# ntp-strat2.net
KiCad netlist of a schematic drawn in EAGLE
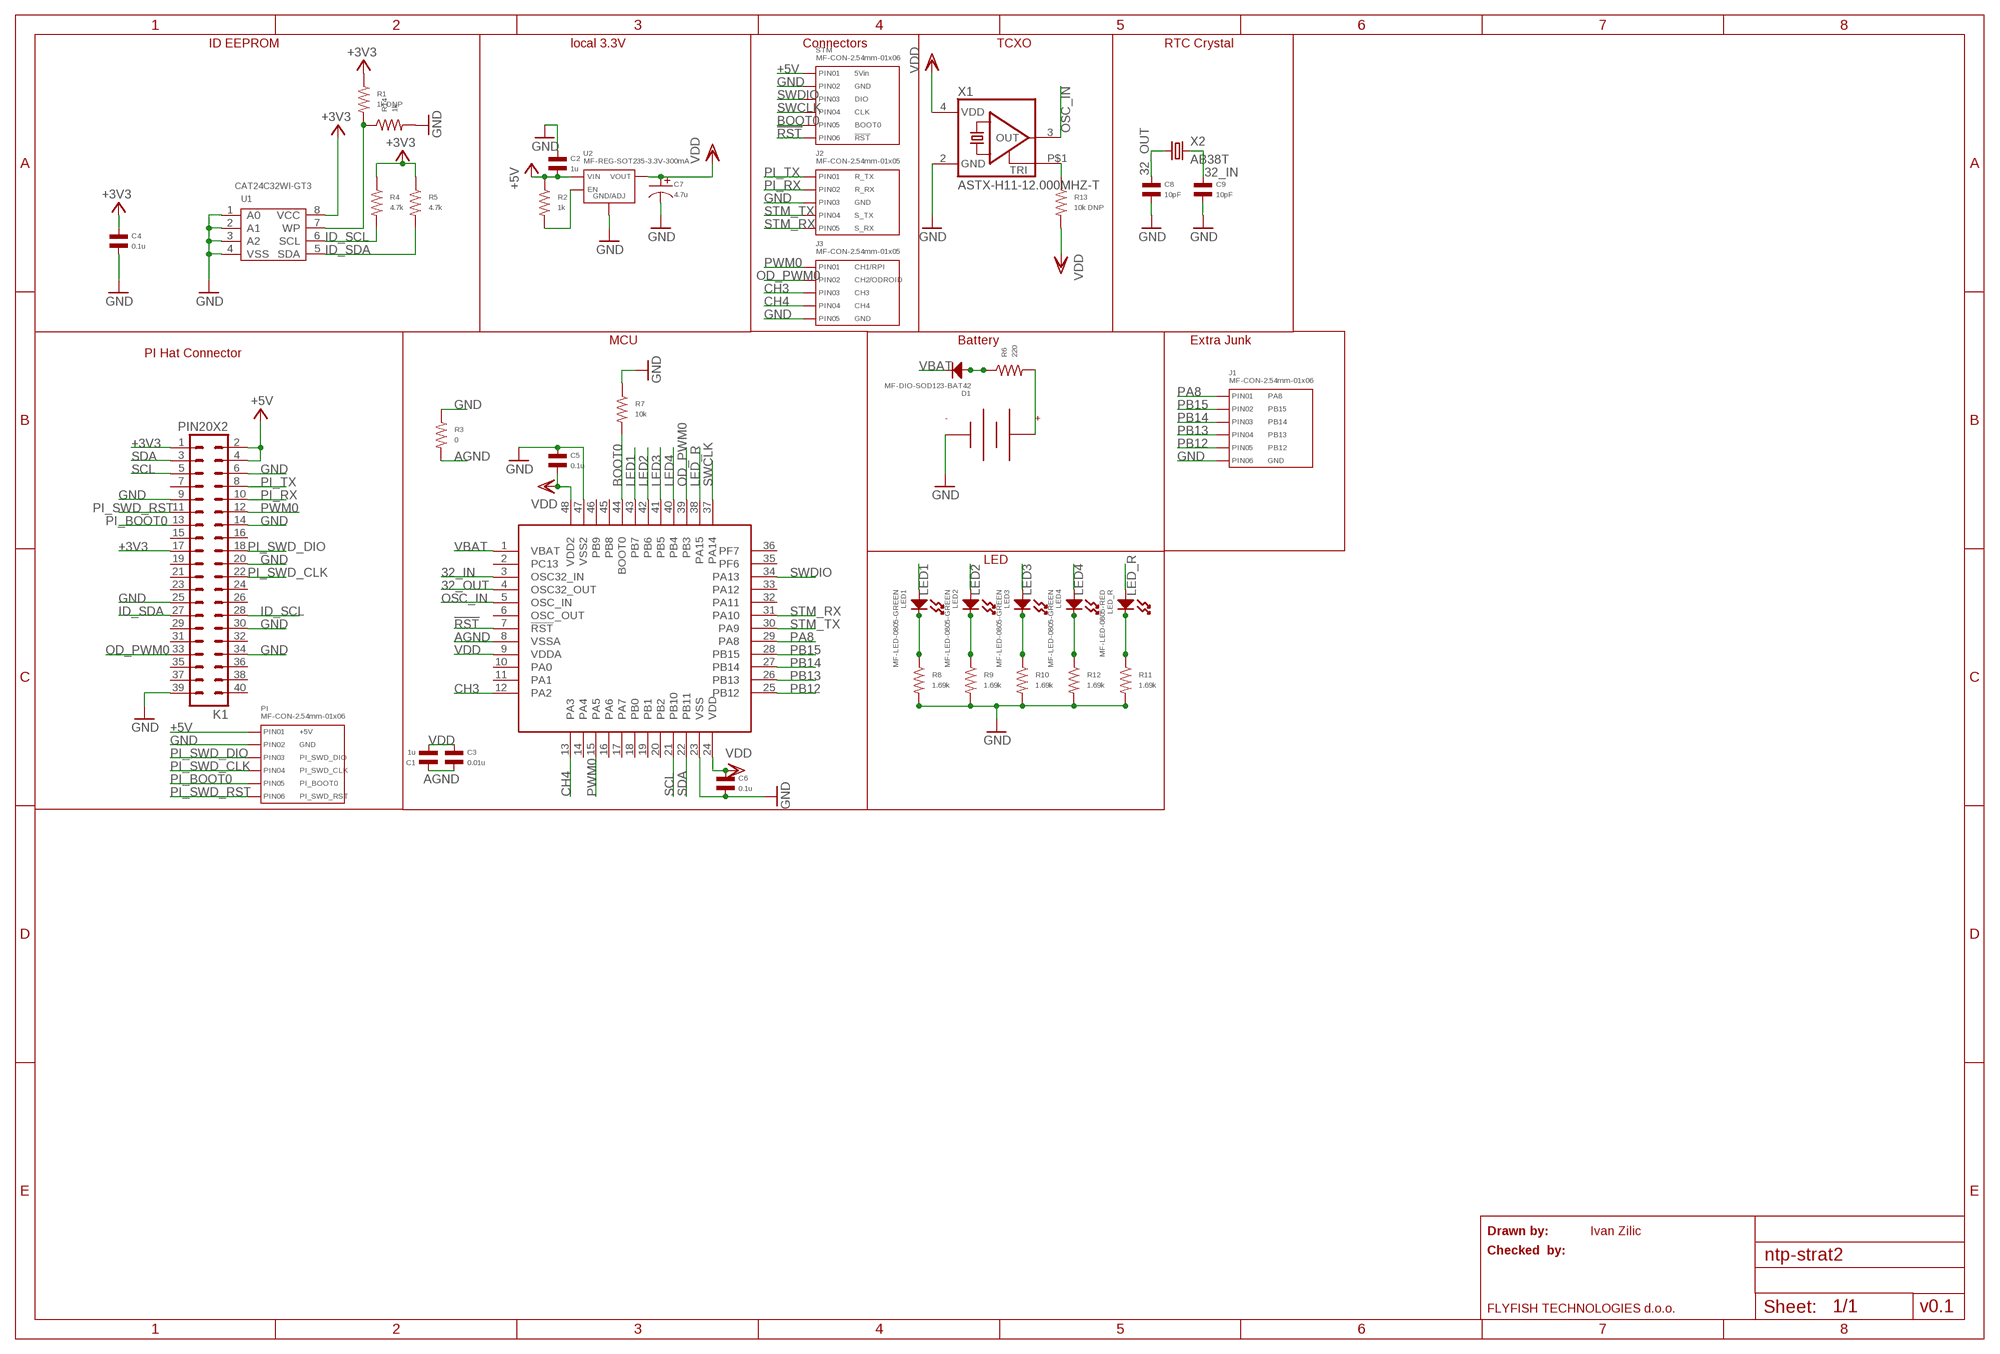
[diagram p0: schematic, sheet 1]

(export (version "E")
  (design (tool "Eeschema 10.0.6"))
  (components
    (comp (ref "C1")
      (value "1u")
      (footprint "eagle-import:C0603")
      (libsource (lib "eagle-import") (part "CAPACITOR_NP_0603"))
    )
    (comp (ref "C2")
      (value "1u")
      (footprint "eagle-import:C0603")
      (libsource (lib "eagle-import") (part "CAPACITOR_NP_0603"))
    )
    (comp (ref "C3")
      (value "0.01u")
      (footprint "eagle-import:C0603")
      (libsource (lib "eagle-import") (part "CAPACITOR_NP_0603"))
    )
    (comp (ref "C4")
      (value "0.1u")
      (footprint "eagle-import:C0603")
      (libsource (lib "eagle-import") (part "CAPACITOR_NP_0603"))
    )
    (comp (ref "C5")
      (value "0.1u")
      (footprint "eagle-import:C0603")
      (libsource (lib "eagle-import") (part "CAPACITOR_NP_0603"))
    )
    (comp (ref "C6")
      (value "0.1u")
      (footprint "eagle-import:C0603")
      (libsource (lib "eagle-import") (part "CAPACITOR_NP_0603"))
    )
    (comp (ref "C7")
      (value "4.7u")
      (footprint "eagle-import:CP4MM")
      (fields (field (name "HOUSEPART") "MF-CAP-4MM-4.7uF"))
      (libsource (lib "eagle-import") (part "CAPACITOR_P_4MM"))
    )
    (comp (ref "C8")
      (value "10pF")
      (footprint "eagle-import:C0603")
      (libsource (lib "eagle-import") (part "CAPACITOR_NP_0603"))
    )
    (comp (ref "C9")
      (value "10pF")
      (footprint "eagle-import:C0603")
      (libsource (lib "eagle-import") (part "CAPACITOR_NP_0603"))
    )
    (comp (ref "D1")
      (value "MF-DIO-SOD123-BAT42")
      (footprint "eagle-import:SOD-123")
      (fields (field (name "HOUSEPART") "YES"))
      (libsource (lib "eagle-import") (part "DIODES_SOD-123_BAT42"))
    )
    (comp (ref "J1")
      (value "MF-CON-2.54mm-01x06")
      (footprint "eagle-import:PTH_2.54MM_01X06")
      (fields
        (field (name "HOUSEPART") "YES")
        (field (name "LABEL01") "PA8")
        (field (name "LABEL02") "PB15")
        (field (name "LABEL03") "PB14")
        (field (name "LABEL04") "PB13")
        (field (name "LABEL05") "PB12")
        (field (name "LABEL06") "GND")
      )
      (libsource (lib "eagle-import") (part "CON_01X06_PTH_2.54MM"))
    )
    (comp (ref "J2")
      (value "MF-CON-2.54mm-01x05")
      (footprint "eagle-import:PTH_2.54MM_01X05")
      (fields
        (field (name "HOUSEPART") "YES")
        (field (name "LABEL01") "R_TX")
        (field (name "LABEL02") "R_RX")
        (field (name "LABEL03") "GND")
        (field (name "LABEL04") "S_TX")
        (field (name "LABEL05") "S_RX")
      )
      (libsource (lib "eagle-import") (part "CON_01X05_PTH_2.54MM"))
    )
    (comp (ref "J3")
      (value "MF-CON-2.54mm-01x05")
      (footprint "eagle-import:PTH_2.54MM_01X05")
      (fields
        (field (name "HOUSEPART") "YES")
        (field (name "LABEL01") "CH1/RPI")
        (field (name "LABEL02") "CH2/ODROID")
        (field (name "LABEL03") "CH3")
        (field (name "LABEL04") "CH4")
        (field (name "LABEL05") "GND")
      )
      (libsource (lib "eagle-import") (part "CON_01X05_PTH_2.54MM"))
    )
    (comp (ref "K1")
      (value "PIN20X2")
      (footprint "eagle-import:PIN_20X2")
      (libsource (lib "eagle-import") (part "PIN20X2"))
    )
    (comp (ref "LED1")
      (value "MF-LED-0805-GREEN")
      (footprint "eagle-import:LED0805")
      (fields (field (name "HOUSEPART") "YES"))
      (libsource (lib "eagle-import") (part "LED_SINGLE-0805-GREEN"))
    )
    (comp (ref "LED2")
      (value "MF-LED-0805-GREEN")
      (footprint "eagle-import:LED0805")
      (fields (field (name "HOUSEPART") "YES"))
      (libsource (lib "eagle-import") (part "LED_SINGLE-0805-GREEN"))
    )
    (comp (ref "LED3")
      (value "MF-LED-0805-GREEN")
      (footprint "eagle-import:LED0805")
      (fields (field (name "HOUSEPART") "YES"))
      (libsource (lib "eagle-import") (part "LED_SINGLE-0805-GREEN"))
    )
    (comp (ref "LED4")
      (value "MF-LED-0805-GREEN")
      (footprint "eagle-import:LED0805")
      (fields (field (name "HOUSEPART") "YES"))
      (libsource (lib "eagle-import") (part "LED_SINGLE-0805-GREEN"))
    )
    (comp (ref "LED_R")
      (value "MF-LED-0805-RED")
      (footprint "eagle-import:LED0805")
      (fields (field (name "HOUSEPART") "YES"))
      (libsource (lib "eagle-import") (part "LED_SINGLE-0805-RED"))
    )
    (comp (ref "PI")
      (value "MF-CON-2.54mm-01x06")
      (footprint "eagle-import:PTH_2.54MM_01X06")
      (fields
        (field (name "HOUSEPART") "YES")
        (field (name "LABEL01") "+5V")
        (field (name "LABEL02") "GND")
        (field (name "LABEL03") "PI_SWD_DIO")
        (field (name "LABEL04") "PI_SWD_CLK")
        (field (name "LABEL05") "PI_BOOT0")
        (field (name "LABEL06") "PI_SWD_RST")
      )
      (libsource (lib "eagle-import") (part "CON_01X06_PTH_2.54MM"))
    )
    (comp (ref "R1")
      (value "1k DNP")
      (footprint "eagle-import:R0603")
      (libsource (lib "eagle-import") (part "RESISTOR_0603"))
    )
    (comp (ref "R2")
      (value "1k")
      (footprint "eagle-import:R0603")
      (libsource (lib "eagle-import") (part "RESISTOR_0603"))
    )
    (comp (ref "R3")
      (value "0")
      (footprint "eagle-import:R0603")
      (libsource (lib "eagle-import") (part "RESISTOR_0603"))
    )
    (comp (ref "R4")
      (value "4.7k")
      (footprint "eagle-import:R0603")
      (libsource (lib "eagle-import") (part "RESISTOR_0603"))
    )
    (comp (ref "R5")
      (value "4.7k")
      (footprint "eagle-import:R0603")
      (libsource (lib "eagle-import") (part "RESISTOR_0603"))
    )
    (comp (ref "R6")
      (value "220")
      (footprint "eagle-import:R0603")
      (libsource (lib "eagle-import") (part "RESISTOR_0603"))
    )
    (comp (ref "R7")
      (value "10k")
      (footprint "eagle-import:R0603")
      (libsource (lib "eagle-import") (part "RESISTOR_0603"))
    )
    (comp (ref "R8")
      (value "1.69k")
      (footprint "eagle-import:R0603")
      (libsource (lib "eagle-import") (part "RESISTOR_0603"))
    )
    (comp (ref "R9")
      (value "1.69k")
      (footprint "eagle-import:R0603")
      (libsource (lib "eagle-import") (part "RESISTOR_0603"))
    )
    (comp (ref "R10")
      (value "1.69k")
      (footprint "eagle-import:R0603")
      (libsource (lib "eagle-import") (part "RESISTOR_0603"))
    )
    (comp (ref "R11")
      (value "1.69k")
      (footprint "eagle-import:R0603")
      (libsource (lib "eagle-import") (part "RESISTOR_0603"))
    )
    (comp (ref "R12")
      (value "1.69k")
      (footprint "eagle-import:R0603")
      (libsource (lib "eagle-import") (part "RESISTOR_0603"))
    )
    (comp (ref "R13")
      (value "10k DNP")
      (footprint "eagle-import:R0603")
      (libsource (lib "eagle-import") (part "RESISTOR_0603"))
    )
    (comp (ref "R14")
      (value "1k")
      (footprint "eagle-import:R0603")
      (libsource (lib "eagle-import") (part "RESISTOR_0603"))
    )
    (comp (ref "STM")
      (value "MF-CON-2.54mm-01x06")
      (footprint "eagle-import:PTH_2.54MM_01X06")
      (fields
        (field (name "HOUSEPART") "YES")
        (field (name "LABEL01") "5Vin")
        (field (name "LABEL02") "GND")
        (field (name "LABEL03") "DIO")
        (field (name "LABEL04") "CLK")
        (field (name "LABEL05") "BOOT0")
        (field (name "LABEL06") "!RST")
      )
      (libsource (lib "eagle-import") (part "CON_01X06_PTH_2.54MM"))
    )
    (comp (ref "U1")
      (value "CAT24C32WI-GT3")
      (footprint "eagle-import:SOIC8-1.27-5X4MM")
      (fields (field (name "MPN") "CAT24C256WI-GT3"))
      (libsource (lib "eagle-import") (part "EEPROM-CAT24C256WI-GT3(SOIC8)"))
    )
    (comp (ref "U2")
      (value "MF-REG-SOT235-3.3V-300mA")
      (footprint "eagle-import:SOT-23-5")
      (fields (field (name "HOUSEPART") "YES") (field (name "MPN") "F-REG-SOT235-3.3V-300mA"))
      (libsource (lib "eagle-import") (part "TLV70233PDBVR"))
    )
    (comp (ref "U3")
      (value "STM32F031C6T6")
      (footprint "eagle-import:LQFP48-7X7")
      (libsource (lib "eagle-import") (part "STM32F031C"))
    )
    (comp (ref "U4")
      (value "BU2032SM-BT-GTR")
      (footprint "eagle-import:BU2032SM")
      (libsource (lib "eagle-import") (part "BU2032SM"))
    )
    (comp (ref "X1")
      (value "ASTX-H11-12.000MHZ-T")
      (footprint "eagle-import:ASVTX")
      (libsource (lib "eagle-import") (part "ASTX-H11"))
    )
    (comp (ref "X2")
      (value "AB38T")
      (footprint "eagle-import:AB38T")
      (libsource (lib "eagle-import") (part "AB38T"))
    )
  )
  (nets
    (net (code "1") (name "+3V3") (class "Default")
      (node (ref "C4") (pin "P$1") (pinfunction "P$1_P$1") (pintype "passive"))
      (node (ref "K1") (pin "1") (pinfunction "1_1") (pintype "passive"))
      (node (ref "K1") (pin "17") (pinfunction "17_17") (pintype "passive"))
      (node (ref "R1") (pin "P$1") (pinfunction "P$1_P$1") (pintype "passive"))
      (node (ref "R4") (pin "P$1") (pinfunction "P$1_P$1") (pintype "passive"))
      (node (ref "R5") (pin "P$1") (pinfunction "P$1_P$1") (pintype "passive"))
      (node (ref "U1") (pin "8") (pinfunction "VCC_8") (pintype "bidirectional"))
    )
    (net (code "2") (name "+5V") (class "Default")
      (node (ref "C2") (pin "P$2") (pinfunction "P$2_P$2") (pintype "passive"))
      (node (ref "K1") (pin "2") (pinfunction "2_2") (pintype "passive"))
      (node (ref "K1") (pin "4") (pinfunction "4_4") (pintype "passive"))
      (node (ref "PI") (pin "P$1") (pinfunction "PIN1_P$1") (pintype "bidirectional"))
      (node (ref "R2") (pin "P$1") (pinfunction "P$1_P$1") (pintype "passive"))
      (node (ref "STM") (pin "P$1") (pinfunction "PIN1_P$1") (pintype "bidirectional"))
      (node (ref "U2") (pin "P$1") (pinfunction "VIN_P$1") (pintype "bidirectional"))
    )
    (net (code "3") (name "/32_IN") (class "Default")
      (node (ref "C9") (pin "P$1") (pinfunction "P$1_P$1") (pintype "passive"))
      (node (ref "U3") (pin "3") (pinfunction "OSC32_IN_3") (pintype "bidirectional"))
      (node (ref "X2") (pin "P2") (pinfunction "2_P2") (pintype "passive"))
    )
    (net (code "4") (name "/32_OUT") (class "Default")
      (node (ref "C8") (pin "P$1") (pinfunction "P$1_P$1") (pintype "passive"))
      (node (ref "U3") (pin "4") (pinfunction "OSC32_OUT_4") (pintype "bidirectional"))
      (node (ref "X2") (pin "P1") (pinfunction "1_P1") (pintype "passive"))
    )
    (net (code "5") (name "/AGND") (class "Default")
      (node (ref "C1") (pin "P$1") (pinfunction "P$1_P$1") (pintype "passive"))
      (node (ref "C3") (pin "P$2") (pinfunction "P$2_P$2") (pintype "passive"))
      (node (ref "R3") (pin "P$2") (pinfunction "P$2_P$2") (pintype "passive"))
      (node (ref "U3") (pin "8") (pinfunction "VSSA_8") (pintype "bidirectional"))
    )
    (net (code "6") (name "/BOOT0") (class "Default")
      (node (ref "R7") (pin "P$2") (pinfunction "P$2_P$2") (pintype "passive"))
      (node (ref "STM") (pin "P$5") (pinfunction "PIN5_P$5") (pintype "bidirectional"))
      (node (ref "U3") (pin "44") (pinfunction "BOOT0_44") (pintype "bidirectional"))
    )
    (net (code "7") (name "/CH3") (class "Default")
      (node (ref "J3") (pin "P$3") (pinfunction "PIN3_P$3") (pintype "bidirectional"))
      (node (ref "U3") (pin "12") (pinfunction "PA2_12") (pintype "bidirectional"))
    )
    (net (code "8") (name "/CH4") (class "Default")
      (node (ref "J3") (pin "P$4") (pinfunction "PIN4_P$4") (pintype "bidirectional"))
      (node (ref "U3") (pin "13") (pinfunction "PA3_13") (pintype "bidirectional"))
    )
    (net (code "9") (name "/ID_SCL") (class "Default")
      (node (ref "K1") (pin "28") (pinfunction "28_28") (pintype "passive"))
      (node (ref "R4") (pin "P$2") (pinfunction "P$2_P$2") (pintype "passive"))
      (node (ref "U1") (pin "6") (pinfunction "SCL_6") (pintype "bidirectional"))
    )
    (net (code "10") (name "/ID_SDA") (class "Default")
      (node (ref "K1") (pin "27") (pinfunction "27_27") (pintype "passive"))
      (node (ref "R5") (pin "P$2") (pinfunction "P$2_P$2") (pintype "passive"))
      (node (ref "U1") (pin "5") (pinfunction "SDA_5") (pintype "bidirectional"))
    )
    (net (code "11") (name "/LED1") (class "Default")
      (node (ref "LED1") (pin "ANODE") (pinfunction "ANODE_ANODE") (pintype "power_in"))
      (node (ref "U3") (pin "43") (pinfunction "PB7_43") (pintype "bidirectional"))
    )
    (net (code "12") (name "/LED2") (class "Default")
      (node (ref "LED2") (pin "ANODE") (pinfunction "ANODE_ANODE") (pintype "power_in"))
      (node (ref "U3") (pin "42") (pinfunction "PB6_42") (pintype "bidirectional"))
    )
    (net (code "13") (name "/LED3") (class "Default")
      (node (ref "LED3") (pin "ANODE") (pinfunction "ANODE_ANODE") (pintype "power_in"))
      (node (ref "U3") (pin "41") (pinfunction "PB5_41") (pintype "bidirectional"))
    )
    (net (code "14") (name "/LED4") (class "Default")
      (node (ref "LED4") (pin "ANODE") (pinfunction "ANODE_ANODE") (pintype "power_in"))
      (node (ref "U3") (pin "40") (pinfunction "PB4_40") (pintype "bidirectional"))
    )
    (net (code "15") (name "/LED_R") (class "Default")
      (node (ref "LED_R") (pin "ANODE") (pinfunction "ANODE_ANODE") (pintype "power_in"))
      (node (ref "U3") (pin "38") (pinfunction "PA15_38") (pintype "bidirectional"))
    )
    (net (code "16") (name "/OD_PWM0") (class "Default")
      (node (ref "J3") (pin "P$2") (pinfunction "PIN2_P$2") (pintype "bidirectional"))
      (node (ref "K1") (pin "33") (pinfunction "33_33") (pintype "passive"))
      (node (ref "U3") (pin "39") (pinfunction "PB3_39") (pintype "bidirectional"))
    )
    (net (code "17") (name "/OSC_IN") (class "Default")
      (node (ref "U3") (pin "5") (pinfunction "OSC_IN_5") (pintype "bidirectional"))
      (node (ref "X1") (pin "3") (pinfunction "OUT_3") (pintype "output"))
    )
    (net (code "18") (name "/PA8") (class "Default")
      (node (ref "J1") (pin "P$1") (pinfunction "PIN1_P$1") (pintype "bidirectional"))
      (node (ref "U3") (pin "29") (pinfunction "PA8_29") (pintype "bidirectional"))
    )
    (net (code "19") (name "/PB12") (class "Default")
      (node (ref "J1") (pin "P$5") (pinfunction "PIN5_P$5") (pintype "bidirectional"))
      (node (ref "U3") (pin "25") (pinfunction "PB12_25") (pintype "bidirectional"))
    )
    (net (code "20") (name "/PB13") (class "Default")
      (node (ref "J1") (pin "P$4") (pinfunction "PIN4_P$4") (pintype "bidirectional"))
      (node (ref "U3") (pin "26") (pinfunction "PB13_26") (pintype "bidirectional"))
    )
    (net (code "21") (name "/PB14") (class "Default")
      (node (ref "J1") (pin "P$3") (pinfunction "PIN3_P$3") (pintype "bidirectional"))
      (node (ref "U3") (pin "27") (pinfunction "PB14_27") (pintype "bidirectional"))
    )
    (net (code "22") (name "/PB15") (class "Default")
      (node (ref "J1") (pin "P$2") (pinfunction "PIN2_P$2") (pintype "bidirectional"))
      (node (ref "U3") (pin "28") (pinfunction "PB15_28") (pintype "bidirectional"))
    )
    (net (code "23") (name "/PI_BOOT0") (class "Default")
      (node (ref "K1") (pin "13") (pinfunction "13_13") (pintype "passive"))
      (node (ref "PI") (pin "P$5") (pinfunction "PIN5_P$5") (pintype "bidirectional"))
    )
    (net (code "24") (name "/PI_RX") (class "Default")
      (node (ref "J2") (pin "P$2") (pinfunction "PIN2_P$2") (pintype "bidirectional"))
      (node (ref "K1") (pin "10") (pinfunction "10_10") (pintype "passive"))
    )
    (net (code "25") (name "/PI_SWD_CLK") (class "Default")
      (node (ref "K1") (pin "22") (pinfunction "22_22") (pintype "passive"))
      (node (ref "PI") (pin "P$4") (pinfunction "PIN4_P$4") (pintype "bidirectional"))
    )
    (net (code "26") (name "/PI_SWD_DIO") (class "Default")
      (node (ref "K1") (pin "18") (pinfunction "18_18") (pintype "passive"))
      (node (ref "PI") (pin "P$3") (pinfunction "PIN3_P$3") (pintype "bidirectional"))
    )
    (net (code "27") (name "/PI_SWD_RST") (class "Default")
      (node (ref "K1") (pin "11") (pinfunction "11_11") (pintype "passive"))
      (node (ref "PI") (pin "P$6") (pinfunction "PIN6_P$6") (pintype "bidirectional"))
    )
    (net (code "28") (name "/PI_TX") (class "Default")
      (node (ref "J2") (pin "P$1") (pinfunction "PIN1_P$1") (pintype "bidirectional"))
      (node (ref "K1") (pin "8") (pinfunction "8_8") (pintype "passive"))
    )
    (net (code "29") (name "/PWM0") (class "Default")
      (node (ref "J3") (pin "P$1") (pinfunction "PIN1_P$1") (pintype "bidirectional"))
      (node (ref "K1") (pin "12") (pinfunction "12_12") (pintype "passive"))
      (node (ref "U3") (pin "15") (pinfunction "PA5_15") (pintype "bidirectional"))
    )
    (net (code "30") (name "/SCL") (class "Default")
      (node (ref "K1") (pin "5") (pinfunction "5_5") (pintype "passive"))
      (node (ref "U3") (pin "21") (pinfunction "PB10_21") (pintype "bidirectional"))
    )
    (net (code "31") (name "/SDA") (class "Default")
      (node (ref "K1") (pin "3") (pinfunction "3_3") (pintype "passive"))
      (node (ref "U3") (pin "22") (pinfunction "PB11_22") (pintype "bidirectional"))
    )
    (net (code "32") (name "/STM_RX") (class "Default")
      (node (ref "J2") (pin "P$5") (pinfunction "PIN5_P$5") (pintype "bidirectional"))
      (node (ref "U3") (pin "31") (pinfunction "PA10_31") (pintype "bidirectional"))
    )
    (net (code "33") (name "/STM_TX") (class "Default")
      (node (ref "J2") (pin "P$4") (pinfunction "PIN4_P$4") (pintype "bidirectional"))
      (node (ref "U3") (pin "30") (pinfunction "PA9_30") (pintype "bidirectional"))
    )
    (net (code "34") (name "/SWCLK") (class "Default")
      (node (ref "STM") (pin "P$4") (pinfunction "PIN4_P$4") (pintype "bidirectional"))
      (node (ref "U3") (pin "37") (pinfunction "PA14_37") (pintype "bidirectional"))
    )
    (net (code "35") (name "/SWDIO") (class "Default")
      (node (ref "STM") (pin "P$3") (pinfunction "PIN3_P$3") (pintype "bidirectional"))
      (node (ref "U3") (pin "34") (pinfunction "PA13_34") (pintype "bidirectional"))
    )
    (net (code "36") (name "/VBAT") (class "Default")
      (node (ref "D1") (pin "CATHODE") (pinfunction "CATHODE_CATHODE") (pintype "bidirectional"))
      (node (ref "U3") (pin "1") (pinfunction "VBAT_1") (pintype "power_in"))
    )
    (net (code "37") (name "/~{RST}") (class "Default")
      (node (ref "STM") (pin "P$6") (pinfunction "PIN6_P$6") (pintype "bidirectional"))
      (node (ref "U3") (pin "7") (pinfunction "~{RST}_7") (pintype "bidirectional"))
    )
    (net (code "38") (name "GND") (class "Default")
      (node (ref "C2") (pin "P$1") (pinfunction "P$1_P$1") (pintype "passive"))
      (node (ref "C4") (pin "P$2") (pinfunction "P$2_P$2") (pintype "passive"))
      (node (ref "C5") (pin "P$1") (pinfunction "P$1_P$1") (pintype "passive"))
      (node (ref "C6") (pin "P$2") (pinfunction "P$2_P$2") (pintype "passive"))
      (node (ref "C7") (pin "P$2") (pinfunction "P$2_P$2") (pintype "passive"))
      (node (ref "C8") (pin "P$2") (pinfunction "P$2_P$2") (pintype "passive"))
      (node (ref "C9") (pin "P$2") (pinfunction "P$2_P$2") (pintype "passive"))
      (node (ref "J1") (pin "P$6") (pinfunction "PIN6_P$6") (pintype "bidirectional"))
      (node (ref "J2") (pin "P$3") (pinfunction "PIN3_P$3") (pintype "bidirectional"))
      (node (ref "J3") (pin "P$5") (pinfunction "PIN5_P$5") (pintype "bidirectional"))
      (node (ref "K1") (pin "14") (pinfunction "14_14") (pintype "passive"))
      (node (ref "K1") (pin "20") (pinfunction "20_20") (pintype "passive"))
      (node (ref "K1") (pin "25") (pinfunction "25_25") (pintype "passive"))
      (node (ref "K1") (pin "30") (pinfunction "30_30") (pintype "passive"))
      (node (ref "K1") (pin "34") (pinfunction "34_34") (pintype "passive"))
      (node (ref "K1") (pin "39") (pinfunction "39_39") (pintype "passive"))
      (node (ref "K1") (pin "6") (pinfunction "6_6") (pintype "passive"))
      (node (ref "K1") (pin "9") (pinfunction "9_9") (pintype "passive"))
      (node (ref "PI") (pin "P$2") (pinfunction "PIN2_P$2") (pintype "bidirectional"))
      (node (ref "R10") (pin "P$2") (pinfunction "P$2_P$2") (pintype "passive"))
      (node (ref "R11") (pin "P$2") (pinfunction "P$2_P$2") (pintype "passive"))
      (node (ref "R12") (pin "P$2") (pinfunction "P$2_P$2") (pintype "passive"))
      (node (ref "R14") (pin "P$2") (pinfunction "P$2_P$2") (pintype "passive"))
      (node (ref "R3") (pin "P$1") (pinfunction "P$1_P$1") (pintype "passive"))
      (node (ref "R7") (pin "P$1") (pinfunction "P$1_P$1") (pintype "passive"))
      (node (ref "R8") (pin "P$2") (pinfunction "P$2_P$2") (pintype "passive"))
      (node (ref "R9") (pin "P$2") (pinfunction "P$2_P$2") (pintype "passive"))
      (node (ref "STM") (pin "P$2") (pinfunction "PIN2_P$2") (pintype "bidirectional"))
      (node (ref "U1") (pin "1") (pinfunction "A0_1") (pintype "bidirectional"))
      (node (ref "U1") (pin "2") (pinfunction "A1_2") (pintype "bidirectional"))
      (node (ref "U1") (pin "3") (pinfunction "A2_3") (pintype "bidirectional"))
      (node (ref "U1") (pin "4") (pinfunction "VSS_4") (pintype "bidirectional"))
      (node (ref "U2") (pin "P$2") (pinfunction "GND/ADJ_P$2") (pintype "bidirectional"))
      (node (ref "U3") (pin "23") (pinfunction "VSS_23") (pintype "bidirectional"))
      (node (ref "U3") (pin "47") (pinfunction "VSS2_47") (pintype "bidirectional"))
      (node (ref "U4") (pin "MINUS") (pinfunction "MINUS_MINUS") (pintype "bidirectional"))
      (node (ref "X1") (pin "2") (pinfunction "GND_2") (pintype "power_in"))
    )
    (net (code "39") (name "Net-(D1-PadANODE)") (class "Default")
      (node (ref "D1") (pin "ANODE") (pinfunction "ANODE_ANODE") (pintype "bidirectional"))
      (node (ref "R6") (pin "P$1") (pinfunction "P$1_P$1") (pintype "passive"))
    )
    (net (code "40") (name "Net-(LED1-PadCATHODE)") (class "Default")
      (node (ref "LED1") (pin "CATHODE") (pinfunction "CATHODE_CATHODE") (pintype "power_in"))
      (node (ref "R8") (pin "P$1") (pinfunction "P$1_P$1") (pintype "passive"))
    )
    (net (code "41") (name "Net-(LED2-PadCATHODE)") (class "Default")
      (node (ref "LED2") (pin "CATHODE") (pinfunction "CATHODE_CATHODE") (pintype "power_in"))
      (node (ref "R9") (pin "P$1") (pinfunction "P$1_P$1") (pintype "passive"))
    )
    (net (code "42") (name "Net-(LED3-PadCATHODE)") (class "Default")
      (node (ref "LED3") (pin "CATHODE") (pinfunction "CATHODE_CATHODE") (pintype "power_in"))
      (node (ref "R10") (pin "P$1") (pinfunction "P$1_P$1") (pintype "passive"))
    )
    (net (code "43") (name "Net-(LED4-PadCATHODE)") (class "Default")
      (node (ref "LED4") (pin "CATHODE") (pinfunction "CATHODE_CATHODE") (pintype "power_in"))
      (node (ref "R12") (pin "P$1") (pinfunction "P$1_P$1") (pintype "passive"))
    )
    (net (code "44") (name "Net-(LED_R-PadCATHODE)") (class "Default")
      (node (ref "LED_R") (pin "CATHODE") (pinfunction "CATHODE_CATHODE") (pintype "power_in"))
      (node (ref "R11") (pin "P$1") (pinfunction "P$1_P$1") (pintype "passive"))
    )
    (net (code "45") (name "Net-(R6-PadP$2)") (class "Default")
      (node (ref "R6") (pin "P$2") (pinfunction "P$2_P$2") (pintype "passive"))
      (node (ref "U4") (pin "PLUS") (pinfunction "PLUS_PLUS") (pintype "bidirectional"))
    )
    (net (code "46") (name "Net-(U1-WP)") (class "Default")
      (node (ref "R1") (pin "P$2") (pinfunction "P$2_P$2") (pintype "passive"))
      (node (ref "R14") (pin "P$1") (pinfunction "P$1_P$1") (pintype "passive"))
      (node (ref "U1") (pin "7") (pinfunction "WP_7") (pintype "bidirectional"))
    )
    (net (code "47") (name "Net-(U2-EN)") (class "Default")
      (node (ref "R2") (pin "P$2") (pinfunction "P$2_P$2") (pintype "passive"))
      (node (ref "U2") (pin "P$3") (pinfunction "EN_P$3") (pintype "bidirectional"))
    )
    (net (code "48") (name "Net-(X1-TRI)") (class "Default")
      (node (ref "R13") (pin "P$1") (pinfunction "P$1_P$1") (pintype "passive"))
      (node (ref "X1") (pin "P$1") (pinfunction "TRI_P$1") (pintype "input"))
    )
    (net (code "49") (name "VDD") (class "Default")
      (node (ref "C1") (pin "P$2") (pinfunction "P$2_P$2") (pintype "passive"))
      (node (ref "C3") (pin "P$1") (pinfunction "P$1_P$1") (pintype "passive"))
      (node (ref "C5") (pin "P$2") (pinfunction "P$2_P$2") (pintype "passive"))
      (node (ref "C6") (pin "P$1") (pinfunction "P$1_P$1") (pintype "passive"))
      (node (ref "C7") (pin "P$1") (pinfunction "P$1_P$1") (pintype "passive"))
      (node (ref "R13") (pin "P$2") (pinfunction "P$2_P$2") (pintype "passive"))
      (node (ref "U2") (pin "P$5") (pinfunction "VOUT_P$5") (pintype "bidirectional"))
      (node (ref "U3") (pin "24") (pinfunction "VDD_24") (pintype "bidirectional"))
      (node (ref "U3") (pin "48") (pinfunction "VDD2_48") (pintype "bidirectional"))
      (node (ref "U3") (pin "9") (pinfunction "VDDA_9") (pintype "bidirectional"))
      (node (ref "X1") (pin "4") (pinfunction "VDD_4") (pintype "power_in"))
    )
    (net (code "50") (name "unconnected-(K1-Pad7)") (class "Default")
      (node (ref "K1") (pin "7") (pinfunction "7_7") (pintype "passive"))
    )
    (net (code "51") (name "unconnected-(K1-Pad15)") (class "Default")
      (node (ref "K1") (pin "15") (pinfunction "15_15") (pintype "passive"))
    )
    (net (code "52") (name "unconnected-(K1-Pad16)") (class "Default")
      (node (ref "K1") (pin "16") (pinfunction "16_16") (pintype "passive"))
    )
    (net (code "53") (name "unconnected-(K1-Pad19)") (class "Default")
      (node (ref "K1") (pin "19") (pinfunction "19_19") (pintype "passive"))
    )
    (net (code "54") (name "unconnected-(K1-Pad21)") (class "Default")
      (node (ref "K1") (pin "21") (pinfunction "21_21") (pintype "passive"))
    )
    (net (code "55") (name "unconnected-(K1-Pad23)") (class "Default")
      (node (ref "K1") (pin "23") (pinfunction "23_23") (pintype "passive"))
    )
    (net (code "56") (name "unconnected-(K1-Pad24)") (class "Default")
      (node (ref "K1") (pin "24") (pinfunction "24_24") (pintype "passive"))
    )
    (net (code "57") (name "unconnected-(K1-Pad26)") (class "Default")
      (node (ref "K1") (pin "26") (pinfunction "26_26") (pintype "passive"))
    )
    (net (code "58") (name "unconnected-(K1-Pad29)") (class "Default")
      (node (ref "K1") (pin "29") (pinfunction "29_29") (pintype "passive"))
    )
    (net (code "59") (name "unconnected-(K1-Pad31)") (class "Default")
      (node (ref "K1") (pin "31") (pinfunction "31_31") (pintype "passive"))
    )
    (net (code "60") (name "unconnected-(K1-Pad32)") (class "Default")
      (node (ref "K1") (pin "32") (pinfunction "32_32") (pintype "passive"))
    )
    (net (code "61") (name "unconnected-(K1-Pad35)") (class "Default")
      (node (ref "K1") (pin "35") (pinfunction "35_35") (pintype "passive"))
    )
    (net (code "62") (name "unconnected-(K1-Pad36)") (class "Default")
      (node (ref "K1") (pin "36") (pinfunction "36_36") (pintype "passive"))
    )
    (net (code "63") (name "unconnected-(K1-Pad37)") (class "Default")
      (node (ref "K1") (pin "37") (pinfunction "37_37") (pintype "passive"))
    )
    (net (code "64") (name "unconnected-(K1-Pad38)") (class "Default")
      (node (ref "K1") (pin "38") (pinfunction "38_38") (pintype "passive"))
    )
    (net (code "65") (name "unconnected-(K1-Pad40)") (class "Default")
      (node (ref "K1") (pin "40") (pinfunction "40_40") (pintype "passive"))
    )
    (net (code "66") (name "unconnected-(U3-OSC_OUT-Pad6)") (class "Default")
      (node (ref "U3") (pin "6") (pinfunction "OSC_OUT_6") (pintype "bidirectional"))
    )
    (net (code "67") (name "unconnected-(U3-PA0-Pad10)") (class "Default")
      (node (ref "U3") (pin "10") (pinfunction "PA0_10") (pintype "bidirectional"))
    )
    (net (code "68") (name "unconnected-(U3-PA1-Pad11)") (class "Default")
      (node (ref "U3") (pin "11") (pinfunction "PA1_11") (pintype "bidirectional"))
    )
    (net (code "69") (name "unconnected-(U3-PA4-Pad14)") (class "Default")
      (node (ref "U3") (pin "14") (pinfunction "PA4_14") (pintype "bidirectional"))
    )
    (net (code "70") (name "unconnected-(U3-PA6-Pad16)") (class "Default")
      (node (ref "U3") (pin "16") (pinfunction "PA6_16") (pintype "bidirectional"))
    )
    (net (code "71") (name "unconnected-(U3-PA7-Pad17)") (class "Default")
      (node (ref "U3") (pin "17") (pinfunction "PA7_17") (pintype "bidirectional"))
    )
    (net (code "72") (name "unconnected-(U3-PA11-Pad32)") (class "Default")
      (node (ref "U3") (pin "32") (pinfunction "PA11_32") (pintype "bidirectional"))
    )
    (net (code "73") (name "unconnected-(U3-PA12-Pad33)") (class "Default")
      (node (ref "U3") (pin "33") (pinfunction "PA12_33") (pintype "bidirectional"))
    )
    (net (code "74") (name "unconnected-(U3-PB0-Pad18)") (class "Default")
      (node (ref "U3") (pin "18") (pinfunction "PB0_18") (pintype "bidirectional"))
    )
    (net (code "75") (name "unconnected-(U3-PB1-Pad19)") (class "Default")
      (node (ref "U3") (pin "19") (pinfunction "PB1_19") (pintype "bidirectional"))
    )
    (net (code "76") (name "unconnected-(U3-PB2-Pad20)") (class "Default")
      (node (ref "U3") (pin "20") (pinfunction "PB2_20") (pintype "bidirectional"))
    )
    (net (code "77") (name "unconnected-(U3-PB8-Pad45)") (class "Default")
      (node (ref "U3") (pin "45") (pinfunction "PB8_45") (pintype "bidirectional"))
    )
    (net (code "78") (name "unconnected-(U3-PB9-Pad46)") (class "Default")
      (node (ref "U3") (pin "46") (pinfunction "PB9_46") (pintype "bidirectional"))
    )
    (net (code "79") (name "unconnected-(U3-PC13-Pad2)") (class "Default")
      (node (ref "U3") (pin "2") (pinfunction "PC13_2") (pintype "bidirectional"))
    )
    (net (code "80") (name "unconnected-(U3-PF6-Pad35)") (class "Default")
      (node (ref "U3") (pin "35") (pinfunction "PF6_35") (pintype "bidirectional"))
    )
    (net (code "81") (name "unconnected-(U3-PF7-Pad36)") (class "Default")
      (node (ref "U3") (pin "36") (pinfunction "PF7_36") (pintype "bidirectional"))
    )
  )
)
